# Electronics_Instrumentation.net
KiCad netlist of a schematic drawn in Altium Designer
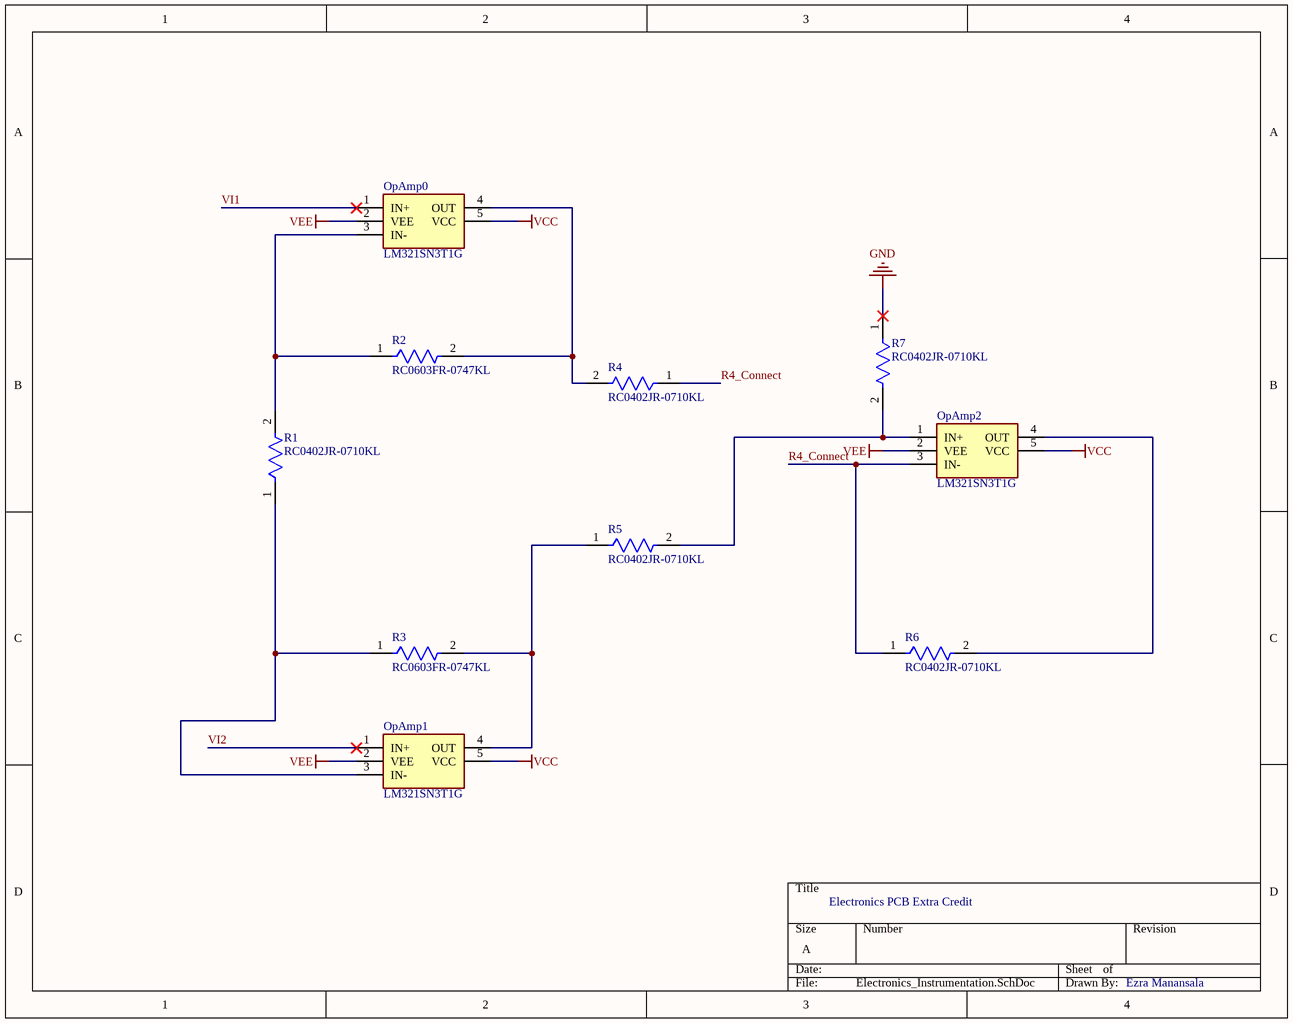
[diagram p0: Electronics_Instrumentation.SchDoc]

(export (version "E")
  (design (tool "Eeschema 10.0.6"))
  (components
    (comp (ref "OpAmp0")
      (value "LM321SN3T1G")
      (footprint "SamacSys:SOT95P275X110-5N")
      (description "Integrated Circuit")
      (fields (field (name "MOUSER PART NUMBER") "863-LM321SN3T1G"))
      (libsource (lib "*") (part "LM321SN3T1G"))
    )
    (comp (ref "OpAmp1")
      (value "LM321SN3T1G")
      (footprint "SamacSys:SOT95P275X110-5N")
      (description "Integrated Circuit")
      (fields (field (name "MOUSER PART NUMBER") "863-LM321SN3T1G"))
      (libsource (lib "*") (part "LM321SN3T1G"))
    )
    (comp (ref "OpAmp2")
      (value "LM321SN3T1G")
      (footprint "SamacSys:SOT95P275X110-5N")
      (description "Integrated Circuit")
      (fields (field (name "MOUSER PART NUMBER") "863-LM321SN3T1G"))
      (libsource (lib "*") (part "LM321SN3T1G"))
    )
    (comp (ref "R1")
      (value "RC0402JR-0710KL")
      (footprint "FP-RC0402-0_4-IPC_C")
      (description "RES 10K OHM 5% 1/16W 0402")
      (fields (field (name "TOLERANCE") "5%"))
      (libsource (lib "Altium Content Vault") (part "1029c3af85768c4190bb7ad29bc67b5"))
    )
    (comp (ref "R2")
      (value "RC0603FR-0747KL")
      (footprint "FP-RC0603FR-0747KL-MFG")
      (description "RES SMD 47K OHM 1% 1/10W 0603")
      (fields (field (name "TOLERANCE") "1%"))
      (libsource (lib "Altium Content Vault") (part "1029c3af85768c4190bb7ad29bc67b5"))
    )
    (comp (ref "R3")
      (value "RC0603FR-0747KL")
      (footprint "FP-RC0603FR-0747KL-MFG")
      (description "RES SMD 47K OHM 1% 1/10W 0603")
      (fields (field (name "TOLERANCE") "1%"))
      (libsource (lib "Altium Content Vault") (part "1029c3af85768c4190bb7ad29bc67b5"))
    )
    (comp (ref "R4")
      (value "RC0402JR-0710KL")
      (footprint "FP-RC0402-0_4-IPC_C")
      (description "RES 10K OHM 5% 1/16W 0402")
      (fields (field (name "TOLERANCE") "5%"))
      (libsource (lib "Altium Content Vault") (part "1029c3af85768c4190bb7ad29bc67b5"))
    )
    (comp (ref "R5")
      (value "RC0402JR-0710KL")
      (footprint "FP-RC0402-0_4-IPC_C")
      (description "RES 10K OHM 5% 1/16W 0402")
      (fields (field (name "TOLERANCE") "5%"))
      (libsource (lib "Altium Content Vault") (part "1029c3af85768c4190bb7ad29bc67b5"))
    )
    (comp (ref "R6")
      (value "RC0402JR-0710KL")
      (footprint "FP-RC0402-0_4-IPC_C")
      (description "RES 10K OHM 5% 1/16W 0402")
      (fields (field (name "TOLERANCE") "5%"))
      (libsource (lib "Altium Content Vault") (part "1029c3af85768c4190bb7ad29bc67b5"))
    )
    (comp (ref "R7")
      (value "RC0402JR-0710KL")
      (footprint "FP-RC0402-0_4-IPC_C")
      (description "RES 10K OHM 5% 1/16W 0402")
      (fields (field (name "TOLERANCE") "5%"))
      (libsource (lib "Altium Content Vault") (part "1029c3af85768c4190bb7ad29bc67b5"))
    )
  )
  (nets
    (net (code "1") (name "/R4_Connect") (class "Default")
      (node (ref "OpAmp2") (pin "3") (pinfunction "IN-_3") (pintype "passive"))
      (node (ref "R4") (pin "1") (pinfunction "1_1") (pintype "passive"))
      (node (ref "R6") (pin "1") (pinfunction "1_1") (pintype "passive"))
    )
    (net (code "2") (name "/VI1") (class "Default")
      (node (ref "OpAmp0") (pin "1") (pinfunction "IN+_1") (pintype "passive+no_connect"))
    )
    (net (code "3") (name "/VI2") (class "Default")
      (node (ref "OpAmp1") (pin "1") (pinfunction "IN+_1") (pintype "passive+no_connect"))
    )
    (net (code "4") (name "GND") (class "Default")
      (node (ref "R7") (pin "1") (pinfunction "1_1") (pintype "passive"))
    )
    (net (code "5") (name "Net-(OpAmp0-IN-)") (class "Default")
      (node (ref "OpAmp0") (pin "3") (pinfunction "IN-_3") (pintype "passive"))
      (node (ref "R1") (pin "2") (pinfunction "2_2") (pintype "passive"))
      (node (ref "R2") (pin "1") (pinfunction "1_1") (pintype "passive"))
    )
    (net (code "6") (name "Net-(OpAmp0-OUT)") (class "Default")
      (node (ref "OpAmp0") (pin "4") (pinfunction "OUT_4") (pintype "passive"))
      (node (ref "R2") (pin "2") (pinfunction "2_2") (pintype "passive"))
      (node (ref "R4") (pin "2") (pinfunction "2_2") (pintype "passive"))
    )
    (net (code "7") (name "Net-(OpAmp1-IN-)") (class "Default")
      (node (ref "OpAmp1") (pin "3") (pinfunction "IN-_3") (pintype "passive"))
      (node (ref "R1") (pin "1") (pinfunction "1_1") (pintype "passive"))
      (node (ref "R3") (pin "1") (pinfunction "1_1") (pintype "passive"))
    )
    (net (code "8") (name "Net-(OpAmp1-OUT)") (class "Default")
      (node (ref "OpAmp1") (pin "4") (pinfunction "OUT_4") (pintype "passive"))
      (node (ref "R3") (pin "2") (pinfunction "2_2") (pintype "passive"))
      (node (ref "R5") (pin "1") (pinfunction "1_1") (pintype "passive"))
    )
    (net (code "9") (name "Net-(OpAmp2-IN+)") (class "Default")
      (node (ref "OpAmp2") (pin "1") (pinfunction "IN+_1") (pintype "passive"))
      (node (ref "R5") (pin "2") (pinfunction "2_2") (pintype "passive"))
      (node (ref "R7") (pin "2") (pinfunction "2_2") (pintype "passive"))
    )
    (net (code "10") (name "Net-(OpAmp2-OUT)") (class "Default")
      (node (ref "OpAmp2") (pin "4") (pinfunction "OUT_4") (pintype "passive"))
      (node (ref "R6") (pin "2") (pinfunction "2_2") (pintype "passive"))
    )
    (net (code "11") (name "VCC") (class "Default")
      (node (ref "OpAmp0") (pin "5") (pinfunction "VCC_5") (pintype "passive"))
      (node (ref "OpAmp1") (pin "5") (pinfunction "VCC_5") (pintype "passive"))
      (node (ref "OpAmp2") (pin "5") (pinfunction "VCC_5") (pintype "passive"))
    )
    (net (code "12") (name "VEE") (class "Default")
      (node (ref "OpAmp0") (pin "2") (pinfunction "VEE_2") (pintype "passive"))
      (node (ref "OpAmp1") (pin "2") (pinfunction "VEE_2") (pintype "passive"))
      (node (ref "OpAmp2") (pin "2") (pinfunction "VEE_2") (pintype "passive"))
    )
  )
)
